# tanfolyamrobot.net
KiCad netlist of a schematic drawn in EAGLE
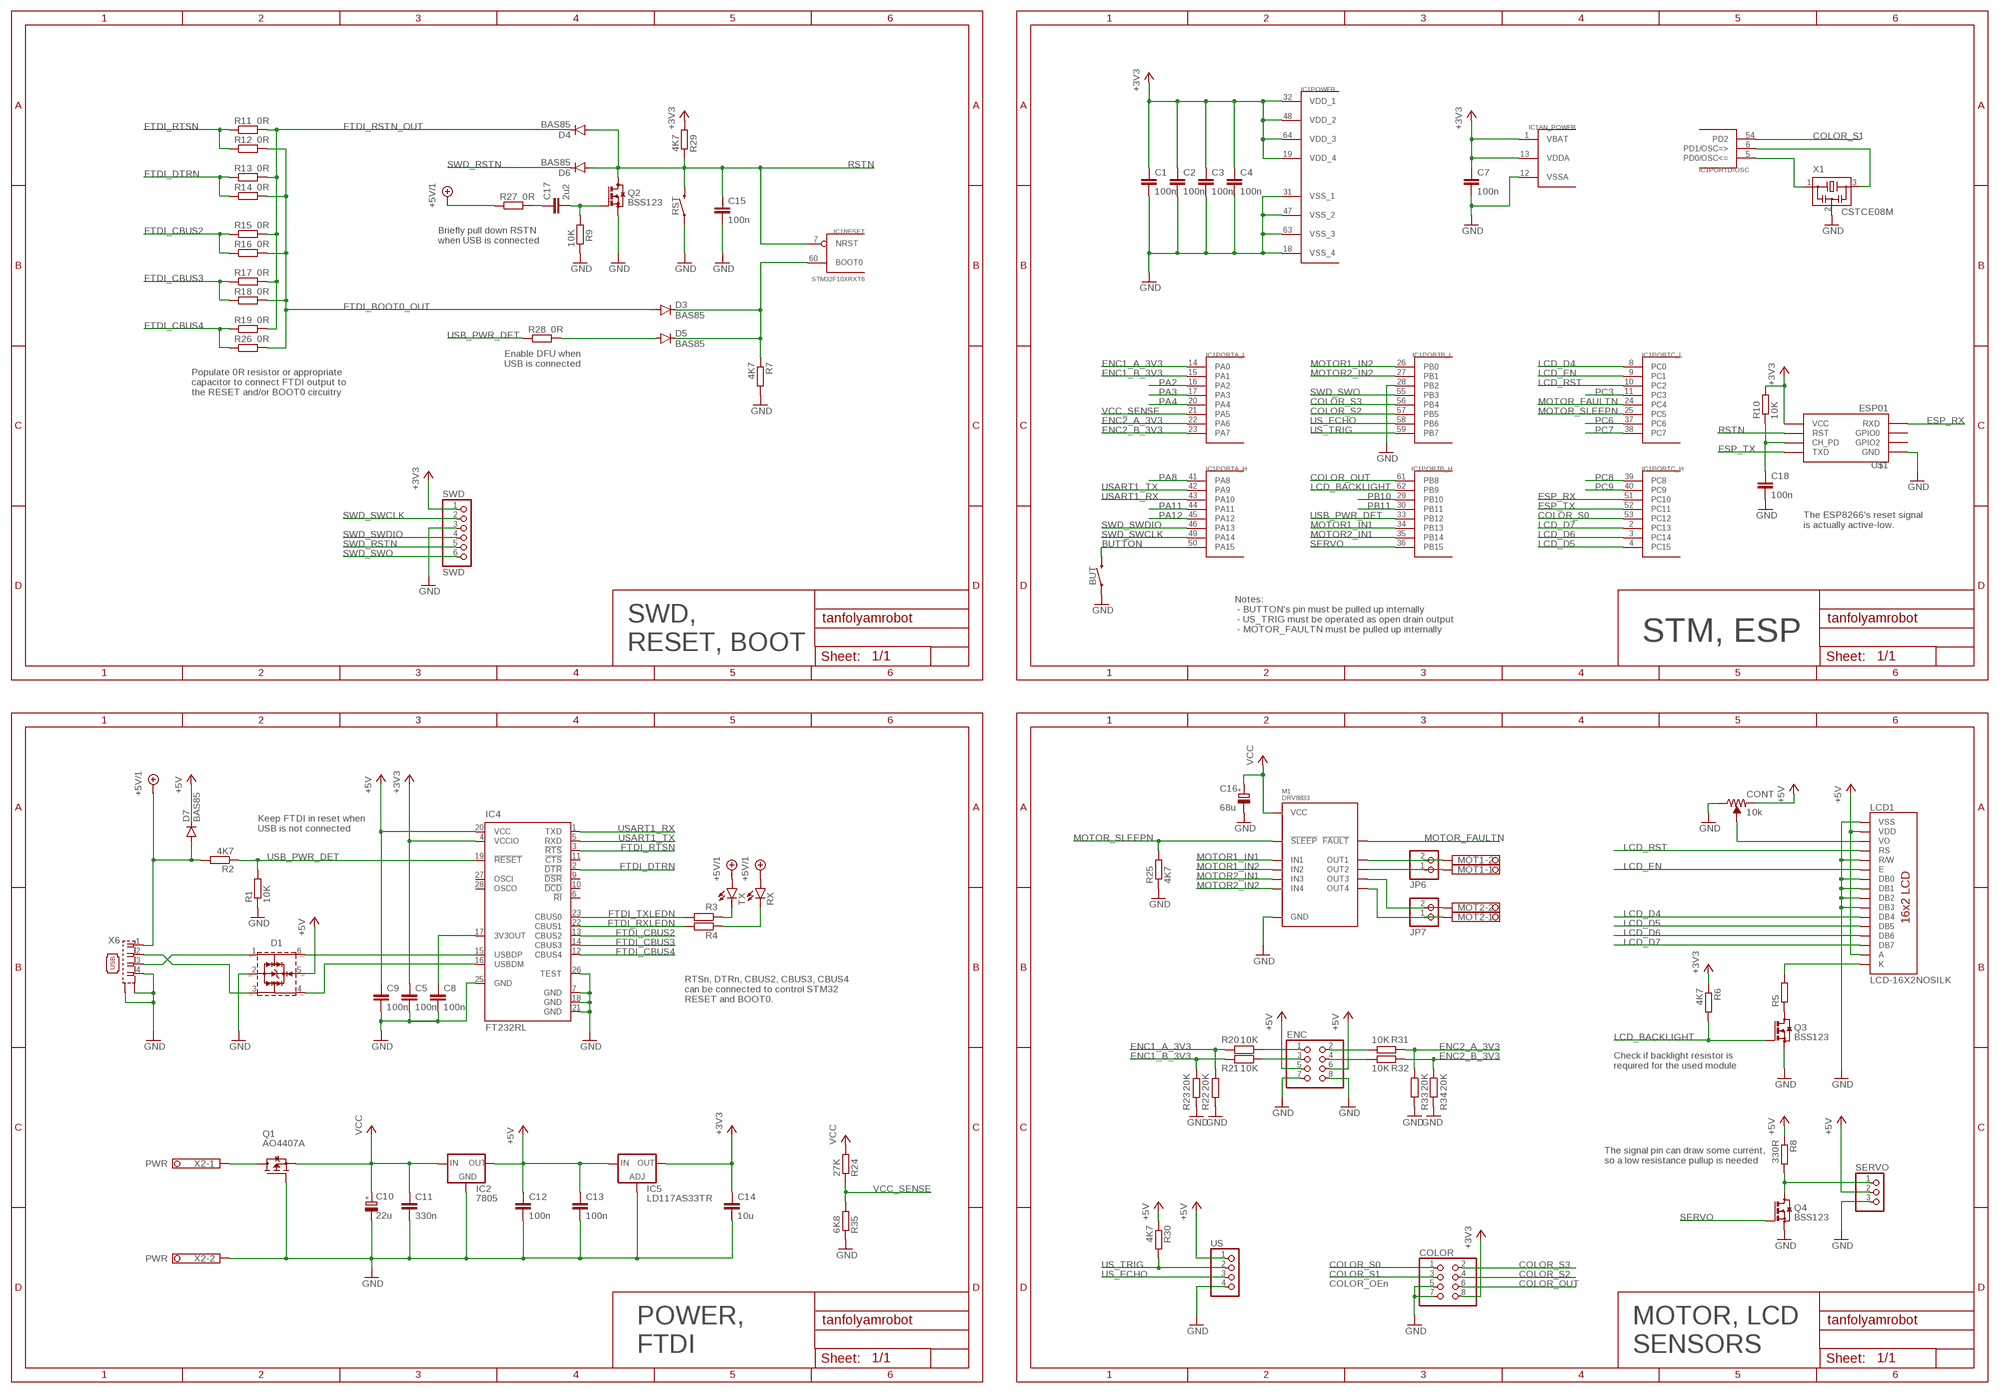
[diagram p0: schematic, sheet 1]

(export (version "E")
  (design (tool "Eeschema 10.0.6"))
  (components
    (comp (ref "BUT")
      (value "MOMENTARY-SWITCH-SPST-PTH-6.0MM")
      (footprint "eagle-import:TACTILE_SWITCH_PTH_6.0MM")
      (libsource (lib "eagle-import") (part "MOMENTARY-SWITCH-SPST-PTH-6.0MM"))
    )
    (comp (ref "C1")
      (value "100n")
      (footprint "eagle-import:C0603")
      (libsource (lib "eagle-import") (part "C-EUC0603"))
    )
    (comp (ref "C2")
      (value "100n")
      (footprint "eagle-import:C0603")
      (libsource (lib "eagle-import") (part "C-EUC0603"))
    )
    (comp (ref "C3")
      (value "100n")
      (footprint "eagle-import:C0603")
      (libsource (lib "eagle-import") (part "C-EUC0603"))
    )
    (comp (ref "C4")
      (value "100n")
      (footprint "eagle-import:C0603")
      (libsource (lib "eagle-import") (part "C-EUC0603"))
    )
    (comp (ref "C5")
      (value "100n")
      (footprint "eagle-import:C0603")
      (libsource (lib "eagle-import") (part "C-EUC0603"))
    )
    (comp (ref "C7")
      (value "100n")
      (footprint "eagle-import:C0603")
      (libsource (lib "eagle-import") (part "C-EUC0603"))
    )
    (comp (ref "C8")
      (value "100n")
      (footprint "eagle-import:C0603")
      (libsource (lib "eagle-import") (part "C-EUC0603"))
    )
    (comp (ref "C9")
      (value "100n")
      (footprint "eagle-import:C0603")
      (libsource (lib "eagle-import") (part "C-EUC0603"))
    )
    (comp (ref "C10")
      (value "22u")
      (footprint "eagle-import:B_3528-21R")
      (libsource (lib "eagle-import") (part "CPOL-EUB/3528-21R"))
    )
    (comp (ref "C11")
      (value "330n")
      (footprint "eagle-import:C0805K")
      (libsource (lib "eagle-import") (part "C-EUC0805K"))
    )
    (comp (ref "C12")
      (value "100n")
      (footprint "eagle-import:C0805K")
      (libsource (lib "eagle-import") (part "C-EUC0805K"))
    )
    (comp (ref "C13")
      (value "100n")
      (footprint "eagle-import:C0805K")
      (libsource (lib "eagle-import") (part "C-EUC0805K"))
    )
    (comp (ref "C14")
      (value "10u")
      (footprint "eagle-import:C0805K")
      (libsource (lib "eagle-import") (part "C-EUC0805K"))
    )
    (comp (ref "C15")
      (value "100n")
      (footprint "eagle-import:C0603")
      (libsource (lib "eagle-import") (part "C-EUC0603"))
    )
    (comp (ref "C16")
      (value "68u")
      (footprint "eagle-import:B_3528-21R")
      (libsource (lib "eagle-import") (part "CPOL-EUB/3528-21R"))
    )
    (comp (ref "C17")
      (value "2u2")
      (footprint "eagle-import:C0603")
      (libsource (lib "eagle-import") (part "C-EUC0603"))
    )
    (comp (ref "C18")
      (value "100n")
      (footprint "eagle-import:C0603")
      (libsource (lib "eagle-import") (part "C-EUC0603"))
    )
    (comp (ref "COLOR")
      (value "PINHD-2X4/90")
      (footprint "eagle-import:2X04_90")
      (libsource (lib "eagle-import") (part "PINHD-2X4/90"))
    )
    (comp (ref "CONT")
      (value "10k")
      (footprint "eagle-import:TRIMPOT-SMD-3MM-CLOSED")
      (libsource (lib "eagle-import") (part "TRIMPOT-SMD-3MM-CLOSED-1/8W-20%"))
    )
    (comp (ref "D1")
      (value "5Vdc")
      (footprint "eagle-import:WE-TVS_SOT23-6L")
      (libsource (lib "eagle-import") (part "WE-TVS-HS_SOT23-6L_82400102"))
    )
    (comp (ref "D3")
      (value "BAS85")
      (footprint "eagle-import:MICROMELF-W")
      (libsource (lib "eagle-import") (part "DIODE-MICROMELF-W"))
    )
    (comp (ref "D4")
      (value "BAS85")
      (footprint "eagle-import:MICROMELF-W")
      (libsource (lib "eagle-import") (part "DIODE-MICROMELF-W"))
    )
    (comp (ref "D5")
      (value "BAS85")
      (footprint "eagle-import:MICROMELF-W")
      (libsource (lib "eagle-import") (part "DIODE-MICROMELF-W"))
    )
    (comp (ref "D6")
      (value "BAS85")
      (footprint "eagle-import:MICROMELF-W")
      (libsource (lib "eagle-import") (part "DIODE-MICROMELF-W"))
    )
    (comp (ref "D7")
      (value "BAS85")
      (footprint "eagle-import:DO-214AC")
      (libsource (lib "eagle-import") (part "DIODE-DO-214AC"))
    )
    (comp (ref "ENC")
      (value "PINHD-2X4/90")
      (footprint "eagle-import:2X04_90")
      (libsource (lib "eagle-import") (part "PINHD-2X4/90"))
    )
    (comp (ref "IC1")
      (value "STM32F10XRXT6")
      (footprint "eagle-import:TQFP64")
      (libsource (lib "eagle-import") (part "STM32F10XRXT6"))
    )
    (comp (ref "IC2")
      (value "7805")
      (footprint "eagle-import:DPACK")
      (libsource (lib "eagle-import") (part "LP2950?CDT-3.0"))
    )
    (comp (ref "IC4")
      (value "FT232RL")
      (footprint "eagle-import:SSOP28")
      (libsource (lib "eagle-import") (part "FT232RL"))
    )
    (comp (ref "IC5")
      (value "LD117AS33TR")
      (footprint "eagle-import:SOT223")
      (libsource (lib "eagle-import") (part "LD117A?S33TR"))
    )
    (comp (ref "JP6")
      (value "PINHD-1X2")
      (footprint "eagle-import:1X02")
      (libsource (lib "eagle-import") (part "PINHD-1X2"))
    )
    (comp (ref "JP7")
      (value "PINHD-1X2")
      (footprint "eagle-import:1X02")
      (libsource (lib "eagle-import") (part "PINHD-1X2"))
    )
    (comp (ref "LCD1")
      (value "LCD-16X2NOSILK")
      (footprint "eagle-import:LCD-16X2_NOSILK")
      (libsource (lib "eagle-import") (part "LCD-16X2NOSILK"))
    )
    (comp (ref "M1")
      (value "DRV8833")
      (footprint "eagle-import:DRV8833_MODULE")
      (libsource (lib "eagle-import") (part "DRV8833"))
    )
    (comp (ref "MOT1")
      (value "PWR")
      (footprint "eagle-import:1751248")
      (libsource (lib "eagle-import") (part "1751248"))
    )
    (comp (ref "MOT2")
      (value "PWR")
      (footprint "eagle-import:1751248")
      (libsource (lib "eagle-import") (part "1751248"))
    )
    (comp (ref "Q1")
      (value "AO4407A")
      (footprint "eagle-import:SO-8")
      (libsource (lib "eagle-import") (part "BSO201SP"))
    )
    (comp (ref "Q2")
      (value "BSS123")
      (footprint "eagle-import:SOT23")
      (libsource (lib "eagle-import") (part "BSS123"))
    )
    (comp (ref "Q3")
      (value "BSS123")
      (footprint "eagle-import:SOT23")
      (libsource (lib "eagle-import") (part "BSS123"))
    )
    (comp (ref "Q4")
      (value "BSS123")
      (footprint "eagle-import:SOT23")
      (libsource (lib "eagle-import") (part "BSS123"))
    )
    (comp (ref "R1")
      (value "10K")
      (footprint "eagle-import:R0603")
      (libsource (lib "eagle-import") (part "R-EU_R0603"))
    )
    (comp (ref "R2")
      (value "4K7")
      (footprint "eagle-import:R0603")
      (libsource (lib "eagle-import") (part "R-EU_R0603"))
    )
    (comp (ref "R3")
      (value "R-EU_R0603")
      (footprint "eagle-import:R0603")
      (libsource (lib "eagle-import") (part "R-EU_R0603"))
    )
    (comp (ref "R4")
      (value "R-EU_R0603")
      (footprint "eagle-import:R0603")
      (libsource (lib "eagle-import") (part "R-EU_R0603"))
    )
    (comp (ref "R5")
      (value "R-EU_R0603")
      (footprint "eagle-import:R0603")
      (libsource (lib "eagle-import") (part "R-EU_R0603"))
    )
    (comp (ref "R6")
      (value "4K7")
      (footprint "eagle-import:R0603")
      (libsource (lib "eagle-import") (part "R-EU_R0603"))
    )
    (comp (ref "R7")
      (value "4K7")
      (footprint "eagle-import:R0603")
      (libsource (lib "eagle-import") (part "R-EU_R0603"))
    )
    (comp (ref "R8")
      (value "330R")
      (footprint "eagle-import:R0603")
      (libsource (lib "eagle-import") (part "R-EU_R0603"))
    )
    (comp (ref "R9")
      (value "10K")
      (footprint "eagle-import:R0603")
      (libsource (lib "eagle-import") (part "R-EU_R0603"))
    )
    (comp (ref "R10")
      (value "10K")
      (footprint "eagle-import:R0603")
      (libsource (lib "eagle-import") (part "R-EU_R0603"))
    )
    (comp (ref "R11")
      (value "0R")
      (footprint "eagle-import:R0603")
      (libsource (lib "eagle-import") (part "R-EU_R0603"))
    )
    (comp (ref "R12")
      (value "0R")
      (footprint "eagle-import:R0603")
      (libsource (lib "eagle-import") (part "R-EU_R0603"))
    )
    (comp (ref "R13")
      (value "0R")
      (footprint "eagle-import:R0603")
      (libsource (lib "eagle-import") (part "R-EU_R0603"))
    )
    (comp (ref "R14")
      (value "0R")
      (footprint "eagle-import:R0603")
      (libsource (lib "eagle-import") (part "R-EU_R0603"))
    )
    (comp (ref "R15")
      (value "0R")
      (footprint "eagle-import:R0603")
      (libsource (lib "eagle-import") (part "R-EU_R0603"))
    )
    (comp (ref "R16")
      (value "0R")
      (footprint "eagle-import:R0603")
      (libsource (lib "eagle-import") (part "R-EU_R0603"))
    )
    (comp (ref "R17")
      (value "0R")
      (footprint "eagle-import:R0603")
      (libsource (lib "eagle-import") (part "R-EU_R0603"))
    )
    (comp (ref "R18")
      (value "0R")
      (footprint "eagle-import:R0603")
      (libsource (lib "eagle-import") (part "R-EU_R0603"))
    )
    (comp (ref "R19")
      (value "0R")
      (footprint "eagle-import:R0603")
      (libsource (lib "eagle-import") (part "R-EU_R0603"))
    )
    (comp (ref "R20")
      (value "10K")
      (footprint "eagle-import:R0603")
      (libsource (lib "eagle-import") (part "R-EU_R0603"))
    )
    (comp (ref "R21")
      (value "10K")
      (footprint "eagle-import:R0603")
      (libsource (lib "eagle-import") (part "R-EU_R0603"))
    )
    (comp (ref "R22")
      (value "20K")
      (footprint "eagle-import:R0603")
      (libsource (lib "eagle-import") (part "R-EU_R0603"))
    )
    (comp (ref "R23")
      (value "20K")
      (footprint "eagle-import:R0603")
      (libsource (lib "eagle-import") (part "R-EU_R0603"))
    )
    (comp (ref "R24")
      (value "27K")
      (footprint "eagle-import:R0603")
      (libsource (lib "eagle-import") (part "R-EU_R0603"))
    )
    (comp (ref "R25")
      (value "4K7")
      (footprint "eagle-import:R0603")
      (libsource (lib "eagle-import") (part "R-EU_R0603"))
    )
    (comp (ref "R26")
      (value "0R")
      (footprint "eagle-import:R0603")
      (libsource (lib "eagle-import") (part "R-EU_R0603"))
    )
    (comp (ref "R27")
      (value "0R")
      (footprint "eagle-import:R0603")
      (libsource (lib "eagle-import") (part "R-EU_R0603"))
    )
    (comp (ref "R28")
      (value "0R")
      (footprint "eagle-import:R0603")
      (libsource (lib "eagle-import") (part "R-EU_R0603"))
    )
    (comp (ref "R29")
      (value "4K7")
      (footprint "eagle-import:R0603")
      (libsource (lib "eagle-import") (part "R-EU_R0603"))
    )
    (comp (ref "R30")
      (value "4K7")
      (footprint "eagle-import:R0603")
      (libsource (lib "eagle-import") (part "R-EU_R0603"))
    )
    (comp (ref "R31")
      (value "10K")
      (footprint "eagle-import:R0603")
      (libsource (lib "eagle-import") (part "R-EU_R0603"))
    )
    (comp (ref "R32")
      (value "10K")
      (footprint "eagle-import:R0603")
      (libsource (lib "eagle-import") (part "R-EU_R0603"))
    )
    (comp (ref "R33")
      (value "20K")
      (footprint "eagle-import:R0603")
      (libsource (lib "eagle-import") (part "R-EU_R0603"))
    )
    (comp (ref "R34")
      (value "20K")
      (footprint "eagle-import:R0603")
      (libsource (lib "eagle-import") (part "R-EU_R0603"))
    )
    (comp (ref "R35")
      (value "6K8")
      (footprint "eagle-import:R0603")
      (libsource (lib "eagle-import") (part "R-EU_R0603"))
    )
    (comp (ref "RST")
      (value "MOMENTARY-SWITCH-SPST-PTH-6.0MM")
      (footprint "eagle-import:TACTILE_SWITCH_PTH_6.0MM")
      (libsource (lib "eagle-import") (part "MOMENTARY-SWITCH-SPST-PTH-6.0MM"))
    )
    (comp (ref "RX")
      (value "LEDCHIP-LED0603")
      (footprint "eagle-import:CHIP-LED0603")
      (libsource (lib "eagle-import") (part "LEDCHIP-LED0603"))
    )
    (comp (ref "SERVO")
      (value "PINHD-1X3/90")
      (footprint "eagle-import:1X03_90")
      (libsource (lib "eagle-import") (part "PINHD-1X3/90"))
    )
    (comp (ref "SWD")
      (value "SWD")
      (footprint "eagle-import:1X06")
      (libsource (lib "eagle-import") (part "PINHD-1X6"))
    )
    (comp (ref "TX")
      (value "LEDCHIP-LED0603")
      (footprint "eagle-import:CHIP-LED0603")
      (libsource (lib "eagle-import") (part "LEDCHIP-LED0603"))
    )
    (comp (ref "U$1")
      (value "ESP01")
      (footprint "eagle-import:ESP01")
      (libsource (lib "eagle-import") (part "ESP01"))
    )
    (comp (ref "US")
      (value "PINHD-1X4/90")
      (footprint "eagle-import:1X04_90")
      (libsource (lib "eagle-import") (part "PINHD-1X4/90"))
    )
    (comp (ref "X1")
      (value "CSTCE08M")
      (footprint "eagle-import:CSTCE")
      (libsource (lib "eagle-import") (part "MURATA_CSTCE"))
    )
    (comp (ref "X2")
      (value "PWR")
      (footprint "eagle-import:1751248")
      (libsource (lib "eagle-import") (part "1751248"))
    )
    (comp (ref "X6")
      (value "KUSBVX-BS1N")
      (footprint "eagle-import:KUSBVX-BS1N")
      (libsource (lib "eagle-import") (part "KUSBVX-BS1N"))
    )
  )
  (nets
    (net (code "1") (name "+3V3") (class "Default")
      (node (ref "C1") (pin "1") (pinfunction "1_1") (pintype "passive"))
      (node (ref "C14") (pin "1") (pinfunction "1_1") (pintype "passive"))
      (node (ref "C2") (pin "1") (pinfunction "1_1") (pintype "passive"))
      (node (ref "C3") (pin "1") (pinfunction "1_1") (pintype "passive"))
      (node (ref "C4") (pin "1") (pinfunction "1_1") (pintype "passive"))
      (node (ref "C5") (pin "1") (pinfunction "1_1") (pintype "passive"))
      (node (ref "C7") (pin "1") (pinfunction "1_1") (pintype "passive"))
      (node (ref "COLOR") (pin "8") (pinfunction "8_8") (pintype "passive"))
      (node (ref "IC1") (pin "1") (pinfunction "VBAT_1") (pintype "power_in"))
      (node (ref "IC1") (pin "13") (pinfunction "VDDA_13") (pintype "power_in"))
      (node (ref "IC1") (pin "19") (pinfunction "VDD_4_19") (pintype "power_in"))
      (node (ref "IC1") (pin "32") (pinfunction "VDD_1_32") (pintype "power_in"))
      (node (ref "IC1") (pin "48") (pinfunction "VDD_2_48") (pintype "power_in"))
      (node (ref "IC1") (pin "64") (pinfunction "VDD_3_64") (pintype "power_in"))
      (node (ref "IC4") (pin "4") (pinfunction "VCCIO_4") (pintype "power_in"))
      (node (ref "IC5") (pin "4") (pinfunction "OUT_4") (pintype "passive"))
      (node (ref "R10") (pin "2") (pinfunction "2_2") (pintype "passive"))
      (node (ref "R29") (pin "1") (pinfunction "1_1") (pintype "passive"))
      (node (ref "R6") (pin "1") (pinfunction "1_1") (pintype "passive"))
      (node (ref "SWD") (pin "1") (pinfunction "1_1") (pintype "passive"))
      (node (ref "U$1") (pin "VCC") (pinfunction "VCC_VCC") (pintype "bidirectional"))
    )
    (net (code "2") (name "+5V") (class "Default")
      (node (ref "C12") (pin "1") (pinfunction "1_1") (pintype "passive"))
      (node (ref "C13") (pin "1") (pinfunction "1_1") (pintype "passive"))
      (node (ref "C9") (pin "1") (pinfunction "1_1") (pintype "passive"))
      (node (ref "CONT") (pin "1") (pinfunction "CCW_1") (pintype "passive"))
      (node (ref "D1") (pin "5") (pinfunction "VDD_5") (pintype "power_in"))
      (node (ref "D7") (pin "C") (pinfunction "C_C") (pintype "passive"))
      (node (ref "ENC") (pin "5") (pinfunction "5_5") (pintype "passive"))
      (node (ref "ENC") (pin "6") (pinfunction "6_6") (pintype "passive"))
      (node (ref "IC2") (pin "3") (pinfunction "OUT_3") (pintype "passive"))
      (node (ref "IC4") (pin "20") (pinfunction "VCC_20") (pintype "power_in"))
      (node (ref "IC5") (pin "3") (pinfunction "IN_3") (pintype "input"))
      (node (ref "LCD1") (pin "15") (pinfunction "A_15") (pintype "power_in"))
      (node (ref "LCD1") (pin "2") (pinfunction "VDD_2") (pintype "power_in"))
      (node (ref "R30") (pin "1") (pinfunction "1_1") (pintype "passive"))
      (node (ref "R8") (pin "1") (pinfunction "1_1") (pintype "passive"))
      (node (ref "SERVO") (pin "2") (pinfunction "2_2") (pintype "passive"))
      (node (ref "US") (pin "1") (pinfunction "1_1") (pintype "passive"))
    )
    (net (code "3") (name "+5V{slash}1") (class "Default")
      (node (ref "D7") (pin "A") (pinfunction "A_A") (pintype "passive"))
      (node (ref "R2") (pin "2") (pinfunction "2_2") (pintype "passive"))
      (node (ref "R27") (pin "1") (pinfunction "1_1") (pintype "passive"))
      (node (ref "RX") (pin "A") (pinfunction "A_A") (pintype "passive"))
      (node (ref "TX") (pin "A") (pinfunction "A_A") (pintype "passive"))
      (node (ref "X6") (pin "1") (pinfunction "1_1") (pintype "passive"))
    )
    (net (code "4") (name "/BUTTON") (class "Default")
      (node (ref "BUT") (pin "3") (pinfunction "2_3") (pintype "passive"))
      (node (ref "IC1") (pin "50") (pinfunction "PA15_50") (pintype "bidirectional"))
    )
    (net (code "5") (name "/COLOR_OUT") (class "Default")
      (node (ref "COLOR") (pin "6") (pinfunction "6_6") (pintype "passive"))
      (node (ref "IC1") (pin "61") (pinfunction "PB8_61") (pintype "bidirectional"))
    )
    (net (code "6") (name "/COLOR_S0") (class "Default")
      (node (ref "COLOR") (pin "1") (pinfunction "1_1") (pintype "passive"))
      (node (ref "IC1") (pin "53") (pinfunction "PC12_53") (pintype "bidirectional"))
    )
    (net (code "7") (name "/COLOR_S1") (class "Default")
      (node (ref "COLOR") (pin "3") (pinfunction "3_3") (pintype "passive"))
      (node (ref "IC1") (pin "54") (pinfunction "PD2_54") (pintype "bidirectional"))
    )
    (net (code "8") (name "/COLOR_S2") (class "Default")
      (node (ref "COLOR") (pin "4") (pinfunction "4_4") (pintype "passive"))
      (node (ref "IC1") (pin "57") (pinfunction "PB5_57") (pintype "bidirectional"))
    )
    (net (code "9") (name "/COLOR_S3") (class "Default")
      (node (ref "COLOR") (pin "2") (pinfunction "2_2") (pintype "passive"))
      (node (ref "IC1") (pin "56") (pinfunction "PB4_56") (pintype "bidirectional"))
    )
    (net (code "10") (name "/ENC1_A_3V3") (class "Default")
      (node (ref "IC1") (pin "14") (pinfunction "PA0_14") (pintype "bidirectional"))
      (node (ref "R20") (pin "2") (pinfunction "2_2") (pintype "passive"))
      (node (ref "R22") (pin "1") (pinfunction "1_1") (pintype "passive"))
    )
    (net (code "11") (name "/ENC1_B_3V3") (class "Default")
      (node (ref "IC1") (pin "15") (pinfunction "PA1_15") (pintype "bidirectional"))
      (node (ref "R21") (pin "2") (pinfunction "2_2") (pintype "passive"))
      (node (ref "R23") (pin "1") (pinfunction "1_1") (pintype "passive"))
    )
    (net (code "12") (name "/ENC2_A_3V3") (class "Default")
      (node (ref "IC1") (pin "22") (pinfunction "PA6_22") (pintype "bidirectional"))
      (node (ref "R31") (pin "2") (pinfunction "2_2") (pintype "passive"))
      (node (ref "R33") (pin "1") (pinfunction "1_1") (pintype "passive"))
    )
    (net (code "13") (name "/ENC2_B_3V3") (class "Default")
      (node (ref "IC1") (pin "23") (pinfunction "PA7_23") (pintype "bidirectional"))
      (node (ref "R32") (pin "2") (pinfunction "2_2") (pintype "passive"))
      (node (ref "R34") (pin "1") (pinfunction "1_1") (pintype "passive"))
    )
    (net (code "14") (name "/ESP_RX") (class "Default")
      (node (ref "IC1") (pin "51") (pinfunction "PC10_51") (pintype "bidirectional"))
      (node (ref "U$1") (pin "RX") (pinfunction "RXD_RX") (pintype "bidirectional"))
    )
    (net (code "15") (name "/ESP_TX") (class "Default")
      (node (ref "IC1") (pin "52") (pinfunction "PC11_52") (pintype "bidirectional"))
      (node (ref "U$1") (pin "TX") (pinfunction "TXD_TX") (pintype "bidirectional"))
    )
    (net (code "16") (name "/FTDI_BOOT0_OUT") (class "Default")
      (node (ref "D3") (pin "A") (pinfunction "A_A") (pintype "passive"))
      (node (ref "R12") (pin "2") (pinfunction "2_2") (pintype "passive"))
      (node (ref "R14") (pin "2") (pinfunction "2_2") (pintype "passive"))
      (node (ref "R16") (pin "2") (pinfunction "2_2") (pintype "passive"))
      (node (ref "R18") (pin "2") (pinfunction "2_2") (pintype "passive"))
      (node (ref "R26") (pin "2") (pinfunction "2_2") (pintype "passive"))
    )
    (net (code "17") (name "/FTDI_CBUS2") (class "Default")
      (node (ref "IC4") (pin "13") (pinfunction "CBUS2_13") (pintype "bidirectional"))
      (node (ref "R15") (pin "1") (pinfunction "1_1") (pintype "passive"))
      (node (ref "R16") (pin "1") (pinfunction "1_1") (pintype "passive"))
    )
    (net (code "18") (name "/FTDI_CBUS3") (class "Default")
      (node (ref "IC4") (pin "14") (pinfunction "CBUS3_14") (pintype "bidirectional"))
      (node (ref "R17") (pin "1") (pinfunction "1_1") (pintype "passive"))
      (node (ref "R18") (pin "1") (pinfunction "1_1") (pintype "passive"))
    )
    (net (code "19") (name "/FTDI_CBUS4") (class "Default")
      (node (ref "IC4") (pin "12") (pinfunction "CBUS4_12") (pintype "bidirectional"))
      (node (ref "R19") (pin "1") (pinfunction "1_1") (pintype "passive"))
      (node (ref "R26") (pin "1") (pinfunction "1_1") (pintype "passive"))
    )
    (net (code "20") (name "/FTDI_DTRN") (class "Default")
      (node (ref "IC4") (pin "2") (pinfunction "~{DTR}_2") (pintype "output"))
      (node (ref "R13") (pin "1") (pinfunction "1_1") (pintype "passive"))
      (node (ref "R14") (pin "1") (pinfunction "1_1") (pintype "passive"))
    )
    (net (code "21") (name "/FTDI_RSTN_OUT") (class "Default")
      (node (ref "D4") (pin "C") (pinfunction "C_C") (pintype "passive"))
      (node (ref "R11") (pin "2") (pinfunction "2_2") (pintype "passive"))
      (node (ref "R13") (pin "2") (pinfunction "2_2") (pintype "passive"))
      (node (ref "R15") (pin "2") (pinfunction "2_2") (pintype "passive"))
      (node (ref "R17") (pin "2") (pinfunction "2_2") (pintype "passive"))
      (node (ref "R19") (pin "2") (pinfunction "2_2") (pintype "passive"))
    )
    (net (code "22") (name "/FTDI_RTSN") (class "Default")
      (node (ref "IC4") (pin "3") (pinfunction "~{RTS}_3") (pintype "output"))
      (node (ref "R11") (pin "1") (pinfunction "1_1") (pintype "passive"))
      (node (ref "R12") (pin "1") (pinfunction "1_1") (pintype "passive"))
    )
    (net (code "23") (name "/FTDI_RXLEDN") (class "Default")
      (node (ref "IC4") (pin "22") (pinfunction "CBUS1_22") (pintype "bidirectional"))
      (node (ref "R4") (pin "2") (pinfunction "2_2") (pintype "passive"))
    )
    (net (code "24") (name "/FTDI_TXLEDN") (class "Default")
      (node (ref "IC4") (pin "23") (pinfunction "CBUS0_23") (pintype "bidirectional"))
      (node (ref "R3") (pin "2") (pinfunction "2_2") (pintype "passive"))
    )
    (net (code "25") (name "/LCD_BACKLIGHT") (class "Default")
      (node (ref "IC1") (pin "62") (pinfunction "PB9_62") (pintype "bidirectional"))
      (node (ref "Q3") (pin "1") (pinfunction "G_1") (pintype "passive"))
      (node (ref "R6") (pin "2") (pinfunction "2_2") (pintype "passive"))
    )
    (net (code "26") (name "/LCD_D4") (class "Default")
      (node (ref "IC1") (pin "8") (pinfunction "PC0_8") (pintype "bidirectional"))
      (node (ref "LCD1") (pin "11") (pinfunction "DB4_11") (pintype "bidirectional"))
    )
    (net (code "27") (name "/LCD_D5") (class "Default")
      (node (ref "IC1") (pin "4") (pinfunction "PC15_4") (pintype "bidirectional"))
      (node (ref "LCD1") (pin "12") (pinfunction "DB5_12") (pintype "bidirectional"))
    )
    (net (code "28") (name "/LCD_D6") (class "Default")
      (node (ref "IC1") (pin "3") (pinfunction "PC14_3") (pintype "bidirectional"))
      (node (ref "LCD1") (pin "13") (pinfunction "DB6_13") (pintype "bidirectional"))
    )
    (net (code "29") (name "/LCD_D7") (class "Default")
      (node (ref "IC1") (pin "2") (pinfunction "PC13_2") (pintype "bidirectional"))
      (node (ref "LCD1") (pin "14") (pinfunction "DB7_14") (pintype "bidirectional"))
    )
    (net (code "30") (name "/LCD_EN") (class "Default")
      (node (ref "IC1") (pin "9") (pinfunction "PC1_9") (pintype "bidirectional"))
      (node (ref "LCD1") (pin "6") (pinfunction "E_6") (pintype "input"))
    )
    (net (code "31") (name "/LCD_RST") (class "Default")
      (node (ref "IC1") (pin "10") (pinfunction "PC2_10") (pintype "bidirectional"))
      (node (ref "LCD1") (pin "4") (pinfunction "RS_4") (pintype "input"))
    )
    (net (code "32") (name "/MOTOR1_IN1") (class "Default")
      (node (ref "IC1") (pin "34") (pinfunction "PB13_34") (pintype "bidirectional"))
      (node (ref "M1") (pin "IN1") (pinfunction "IN1_IN1") (pintype "bidirectional"))
    )
    (net (code "33") (name "/MOTOR1_IN2") (class "Default")
      (node (ref "IC1") (pin "26") (pinfunction "PB0_26") (pintype "bidirectional"))
      (node (ref "M1") (pin "IN2") (pinfunction "IN2_IN2") (pintype "bidirectional"))
    )
    (net (code "34") (name "/MOTOR2_IN1") (class "Default")
      (node (ref "IC1") (pin "35") (pinfunction "PB14_35") (pintype "bidirectional"))
      (node (ref "M1") (pin "IN3") (pinfunction "IN3_IN3") (pintype "bidirectional"))
    )
    (net (code "35") (name "/MOTOR2_IN2") (class "Default")
      (node (ref "IC1") (pin "27") (pinfunction "PB1_27") (pintype "bidirectional"))
      (node (ref "M1") (pin "IN4") (pinfunction "IN4_IN4") (pintype "bidirectional"))
    )
    (net (code "36") (name "/MOTOR_FAULTN") (class "Default")
      (node (ref "IC1") (pin "24") (pinfunction "PC4_24") (pintype "bidirectional"))
      (node (ref "M1") (pin "!FAULT") (pinfunction "~{FAULT}_!FAULT") (pintype "bidirectional"))
    )
    (net (code "37") (name "/MOTOR_SLEEPN") (class "Default")
      (node (ref "IC1") (pin "25") (pinfunction "PC5_25") (pintype "bidirectional"))
      (node (ref "M1") (pin "!SLEEP") (pinfunction "~{SLEEP}_!SLEEP") (pintype "bidirectional"))
      (node (ref "R25") (pin "2") (pinfunction "2_2") (pintype "passive"))
    )
    (net (code "38") (name "/PA2") (class "Default")
      (node (ref "IC1") (pin "16") (pinfunction "PA2_16") (pintype "bidirectional"))
    )
    (net (code "39") (name "/PA3") (class "Default")
      (node (ref "IC1") (pin "17") (pinfunction "PA3_17") (pintype "bidirectional"))
    )
    (net (code "40") (name "/PA4") (class "Default")
      (node (ref "IC1") (pin "20") (pinfunction "PA4_20") (pintype "bidirectional"))
    )
    (net (code "41") (name "/PA8") (class "Default")
      (node (ref "IC1") (pin "41") (pinfunction "PA8_41") (pintype "bidirectional"))
    )
    (net (code "42") (name "/PA11") (class "Default")
      (node (ref "IC1") (pin "44") (pinfunction "PA11_44") (pintype "bidirectional"))
    )
    (net (code "43") (name "/PA12") (class "Default")
      (node (ref "IC1") (pin "45") (pinfunction "PA12_45") (pintype "bidirectional"))
    )
    (net (code "44") (name "/PB10") (class "Default")
      (node (ref "IC1") (pin "29") (pinfunction "PB10_29") (pintype "bidirectional"))
    )
    (net (code "45") (name "/PB11") (class "Default")
      (node (ref "IC1") (pin "30") (pinfunction "PB11_30") (pintype "bidirectional"))
    )
    (net (code "46") (name "/PC3") (class "Default")
      (node (ref "IC1") (pin "11") (pinfunction "PC3_11") (pintype "bidirectional"))
    )
    (net (code "47") (name "/PC6") (class "Default")
      (node (ref "IC1") (pin "37") (pinfunction "PC6_37") (pintype "bidirectional"))
    )
    (net (code "48") (name "/PC7") (class "Default")
      (node (ref "IC1") (pin "38") (pinfunction "PC7_38") (pintype "bidirectional"))
    )
    (net (code "49") (name "/PC8") (class "Default")
      (node (ref "IC1") (pin "39") (pinfunction "PC8_39") (pintype "bidirectional"))
    )
    (net (code "50") (name "/PC9") (class "Default")
      (node (ref "IC1") (pin "40") (pinfunction "PC9_40") (pintype "bidirectional"))
    )
    (net (code "51") (name "/RSTN") (class "Default")
      (node (ref "C15") (pin "1") (pinfunction "1_1") (pintype "passive"))
      (node (ref "D4") (pin "A") (pinfunction "A_A") (pintype "passive"))
      (node (ref "D6") (pin "A") (pinfunction "A_A") (pintype "passive"))
      (node (ref "IC1") (pin "7") (pinfunction "NRST_7") (pintype "input"))
      (node (ref "Q2") (pin "3") (pinfunction "D_3") (pintype "passive"))
      (node (ref "R29") (pin "2") (pinfunction "2_2") (pintype "passive"))
      (node (ref "RST") (pin "3") (pinfunction "2_3") (pintype "passive"))
      (node (ref "U$1") (pin "RST") (pinfunction "RST_RST") (pintype "bidirectional"))
    )
    (net (code "52") (name "/SERVO") (class "Default")
      (node (ref "IC1") (pin "36") (pinfunction "PB15_36") (pintype "bidirectional"))
      (node (ref "Q4") (pin "1") (pinfunction "G_1") (pintype "passive"))
    )
    (net (code "53") (name "/SWD_RSTN") (class "Default")
      (node (ref "D6") (pin "C") (pinfunction "C_C") (pintype "passive"))
      (node (ref "SWD") (pin "5") (pinfunction "5_5") (pintype "passive"))
    )
    (net (code "54") (name "/SWD_SWCLK") (class "Default")
      (node (ref "IC1") (pin "49") (pinfunction "PA14_49") (pintype "bidirectional"))
      (node (ref "SWD") (pin "2") (pinfunction "2_2") (pintype "passive"))
    )
    (net (code "55") (name "/SWD_SWDIO") (class "Default")
      (node (ref "IC1") (pin "46") (pinfunction "PA13_46") (pintype "bidirectional"))
      (node (ref "SWD") (pin "4") (pinfunction "4_4") (pintype "passive"))
    )
    (net (code "56") (name "/SWD_SWO") (class "Default")
      (node (ref "IC1") (pin "55") (pinfunction "PB3_55") (pintype "bidirectional"))
      (node (ref "SWD") (pin "6") (pinfunction "6_6") (pintype "passive"))
    )
    (net (code "57") (name "/USART1_RX") (class "Default")
      (node (ref "IC1") (pin "43") (pinfunction "PA10_43") (pintype "bidirectional"))
      (node (ref "IC4") (pin "1") (pinfunction "TXD_1") (pintype "output"))
    )
    (net (code "58") (name "/USART1_TX") (class "Default")
      (node (ref "IC1") (pin "42") (pinfunction "PA9_42") (pintype "bidirectional"))
      (node (ref "IC4") (pin "5") (pinfunction "RXD_5") (pintype "input"))
    )
    (net (code "59") (name "/USB_PWR_DET") (class "Default")
      (node (ref "IC1") (pin "33") (pinfunction "PB12_33") (pintype "bidirectional"))
      (node (ref "IC4") (pin "19") (pinfunction "~{RESET}_19") (pintype "input"))
      (node (ref "R1") (pin "2") (pinfunction "2_2") (pintype "passive"))
      (node (ref "R2") (pin "1") (pinfunction "1_1") (pintype "passive"))
      (node (ref "R28") (pin "1") (pinfunction "1_1") (pintype "passive"))
    )
    (net (code "60") (name "/US_ECHO") (class "Default")
      (node (ref "IC1") (pin "58") (pinfunction "PB6_58") (pintype "bidirectional"))
      (node (ref "US") (pin "3") (pinfunction "3_3") (pintype "passive"))
    )
    (net (code "61") (name "/US_TRIG") (class "Default")
      (node (ref "IC1") (pin "59") (pinfunction "PB7_59") (pintype "bidirectional"))
      (node (ref "R30") (pin "2") (pinfunction "2_2") (pintype "passive"))
      (node (ref "US") (pin "2") (pinfunction "2_2") (pintype "passive"))
    )
    (net (code "62") (name "/VCC_SENSE") (class "Default")
      (node (ref "IC1") (pin "21") (pinfunction "PA5_21") (pintype "bidirectional"))
      (node (ref "R24") (pin "2") (pinfunction "2_2") (pintype "passive"))
      (node (ref "R35") (pin "1") (pinfunction "1_1") (pintype "passive"))
    )
    (net (code "63") (name "GND") (class "Default")
      (node (ref "BUT") (pin "1") (pinfunction "1_1") (pintype "passive"))
      (node (ref "C1") (pin "2") (pinfunction "2_2") (pintype "passive"))
      (node (ref "C10") (pin "-") (pinfunction "-_-") (pintype "passive"))
      (node (ref "C11") (pin "2") (pinfunction "2_2") (pintype "passive"))
      (node (ref "C12") (pin "2") (pinfunction "2_2") (pintype "passive"))
      (node (ref "C13") (pin "2") (pinfunction "2_2") (pintype "passive"))
      (node (ref "C14") (pin "2") (pinfunction "2_2") (pintype "passive"))
      (node (ref "C15") (pin "2") (pinfunction "2_2") (pintype "passive"))
      (node (ref "C16") (pin "-") (pinfunction "-_-") (pintype "passive"))
      (node (ref "C18") (pin "2") (pinfunction "2_2") (pintype "passive"))
      (node (ref "C2") (pin "2") (pinfunction "2_2") (pintype "passive"))
      (node (ref "C3") (pin "2") (pinfunction "2_2") (pintype "passive"))
      (node (ref "C4") (pin "2") (pinfunction "2_2") (pintype "passive"))
      (node (ref "C5") (pin "2") (pinfunction "2_2") (pintype "passive"))
      (node (ref "C7") (pin "2") (pinfunction "2_2") (pintype "passive"))
      (node (ref "C8") (pin "2") (pinfunction "2_2") (pintype "passive"))
      (node (ref "C9") (pin "2") (pinfunction "2_2") (pintype "passive"))
      (node (ref "COLOR") (pin "5") (pinfunction "5_5") (pintype "passive"))
      (node (ref "COLOR") (pin "7") (pinfunction "7_7") (pintype "passive"))
      (node (ref "CONT") (pin "3") (pinfunction "CW_3") (pintype "passive"))
      (node (ref "D1") (pin "2") (pinfunction "GND_2") (pintype "power_in"))
      (node (ref "ENC") (pin "7") (pinfunction "7_7") (pintype "passive"))
      (node (ref "ENC") (pin "8") (pinfunction "8_8") (pintype "passive"))
      (node (ref "IC1") (pin "12") (pinfunction "VSSA_12") (pintype "power_in"))
      (node (ref "IC1") (pin "18") (pinfunction "VSS_4_18") (pintype "power_in"))
      (node (ref "IC1") (pin "28") (pinfunction "PB2_28") (pintype "bidirectional"))
      (node (ref "IC1") (pin "31") (pinfunction "VSS_1_31") (pintype "power_in"))
      (node (ref "IC1") (pin "47") (pinfunction "VSS_2_47") (pintype "power_in"))
      (node (ref "IC1") (pin "63") (pinfunction "VSS_3_63") (pintype "power_in"))
      (node (ref "IC2") (pin "4") (pinfunction "GND_4") (pintype "input"))
      (node (ref "IC4") (pin "18") (pinfunction "GND_18") (pintype "power_in"))
      (node (ref "IC4") (pin "21") (pinfunction "GND_21") (pintype "power_in"))
      (node (ref "IC4") (pin "25") (pinfunction "GND_25") (pintype "power_in"))
      (node (ref "IC4") (pin "26") (pinfunction "TEST_26") (pintype "input"))
      (node (ref "IC4") (pin "7") (pinfunction "GND_7") (pintype "power_in"))
      (node (ref "IC5") (pin "1") (pinfunction "ADJ_1") (pintype "input"))
      (node (ref "LCD1") (pin "1") (pinfunction "VSS_1") (pintype "power_in"))
      (node (ref "LCD1") (pin "10") (pinfunction "DB3_10") (pintype "bidirectional"))
      (node (ref "LCD1") (pin "5") (pinfunction "R/W_5") (pintype "input"))
      (node (ref "LCD1") (pin "7") (pinfunction "DB0_7") (pintype "bidirectional"))
      (node (ref "LCD1") (pin "8") (pinfunction "DB1_8") (pintype "bidirectional"))
      (node (ref "LCD1") (pin "9") (pinfunction "DB2_9") (pintype "bidirectional"))
      (node (ref "M1") (pin "GND") (pinfunction "GND_GND") (pintype "bidirectional"))
      (node (ref "Q1") (pin "4") (pinfunction "G_4") (pintype "passive"))
      (node (ref "Q2") (pin "2") (pinfunction "S_2") (pintype "passive"))
      (node (ref "Q3") (pin "2") (pinfunction "S_2") (pintype "passive"))
      (node (ref "Q4") (pin "2") (pinfunction "S_2") (pintype "passive"))
      (node (ref "R1") (pin "1") (pinfunction "1_1") (pintype "passive"))
      (node (ref "R22") (pin "2") (pinfunction "2_2") (pintype "passive"))
      (node (ref "R23") (pin "2") (pinfunction "2_2") (pintype "passive"))
      (node (ref "R25") (pin "1") (pinfunction "1_1") (pintype "passive"))
      (node (ref "R33") (pin "2") (pinfunction "2_2") (pintype "passive"))
      (node (ref "R34") (pin "2") (pinfunction "2_2") (pintype "passive"))
      (node (ref "R35") (pin "2") (pinfunction "2_2") (pintype "passive"))
      (node (ref "R7") (pin "2") (pinfunction "2_2") (pintype "passive"))
      (node (ref "R9") (pin "2") (pinfunction "2_2") (pintype "passive"))
      (node (ref "RST") (pin "1") (pinfunction "1_1") (pintype "passive"))
      (node (ref "SERVO") (pin "3") (pinfunction "3_3") (pintype "passive"))
      (node (ref "SWD") (pin "3") (pinfunction "3_3") (pintype "passive"))
      (node (ref "U$1") (pin "GND") (pinfunction "GND_GND") (pintype "bidirectional"))
      (node (ref "US") (pin "4") (pinfunction "4_4") (pintype "passive"))
      (node (ref "X1") (pin "2") (pinfunction "2_2") (pintype "passive"))
      (node (ref "X2") (pin "2") (pinfunction "K_2") (pintype "passive"))
      (node (ref "X6") (pin "4") (pinfunction "4_4") (pintype "passive"))
      (node (ref "X6") (pin "M1") (pinfunction "S1_M1") (pintype "passive"))
      (node (ref "X6") (pin "M2") (pinfunction "S2_M2") (pintype "passive"))
    )
    (net (code "64") (name "Net-(C17-Pad1)") (class "Default")
      (node (ref "C17") (pin "1") (pinfunction "1_1") (pintype "passive"))
      (node (ref "R27") (pin "2") (pinfunction "2_2") (pintype "passive"))
    )
    (net (code "65") (name "Net-(C18-Pad1)") (class "Default")
      (node (ref "C18") (pin "1") (pinfunction "1_1") (pintype "passive"))
      (node (ref "R10") (pin "1") (pinfunction "1_1") (pintype "passive"))
      (node (ref "U$1") (pin "CH_PD") (pinfunction "CH_PD_CH_PD") (pintype "bidirectional"))
    )
    (net (code "66") (name "Net-(CONT-WIPER)") (class "Default")
      (node (ref "CONT") (pin "2") (pinfunction "WIPER_2") (pintype "passive"))
      (node (ref "LCD1") (pin "3") (pinfunction "VO_3") (pintype "bidirectional"))
    )
    (net (code "67") (name "Net-(D1-I{slash}O1)") (class "Default")
      (node (ref "D1") (pin "1") (pinfunction "I/O1_1") (pintype "bidirectional"))
      (node (ref "X6") (pin "3") (pinfunction "3_3") (pintype "passive"))
    )
    (net (code "68") (name "Net-(D1-I{slash}O2)") (class "Default")
      (node (ref "D1") (pin "3") (pinfunction "I/O2_3") (pintype "bidirectional"))
      (node (ref "X6") (pin "2") (pinfunction "2_2") (pintype "passive"))
    )
    (net (code "69") (name "Net-(D1-I{slash}O3)") (class "Default")
      (node (ref "D1") (pin "6") (pinfunction "I/O3_6") (pintype "bidirectional"))
      (node (ref "IC4") (pin "15") (pinfunction "USBDP_15") (pintype "bidirectional"))
    )
    (net (code "70") (name "Net-(D1-I{slash}O4)") (class "Default")
      (node (ref "D1") (pin "4") (pinfunction "I/O4_4") (pintype "bidirectional"))
      (node (ref "IC4") (pin "16") (pinfunction "USBDM_16") (pintype "bidirectional"))
    )
    (net (code "71") (name "Net-(D5-PadA)") (class "Default")
      (node (ref "D5") (pin "A") (pinfunction "A_A") (pintype "passive"))
      (node (ref "R28") (pin "2") (pinfunction "2_2") (pintype "passive"))
    )
    (net (code "72") (name "Net-(ENC-Pad1)") (class "Default")
      (node (ref "ENC") (pin "1") (pinfunction "1_1") (pintype "passive"))
      (node (ref "R20") (pin "1") (pinfunction "1_1") (pintype "passive"))
    )
    (net (code "73") (name "Net-(ENC-Pad2)") (class "Default")
      (node (ref "ENC") (pin "2") (pinfunction "2_2") (pintype "passive"))
      (node (ref "R31") (pin "1") (pinfunction "1_1") (pintype "passive"))
    )
    (net (code "74") (name "Net-(ENC-Pad3)") (class "Default")
      (node (ref "ENC") (pin "3") (pinfunction "3_3") (pintype "passive"))
      (node (ref "R21") (pin "1") (pinfunction "1_1") (pintype "passive"))
    )
    (net (code "75") (name "Net-(ENC-Pad4)") (class "Default")
      (node (ref "ENC") (pin "4") (pinfunction "4_4") (pintype "passive"))
      (node (ref "R32") (pin "1") (pinfunction "1_1") (pintype "passive"))
    )
    (net (code "76") (name "Net-(IC1H-PD0{slash}OSC<=)") (class "Default")
      (node (ref "IC1") (pin "5") (pinfunction "PD0/OSC<=_5") (pintype "bidirectional"))
      (node (ref "X1") (pin "1") (pinfunction "1_1") (pintype "passive"))
    )
    (net (code "77") (name "Net-(IC1H-PD1{slash}OSC=>)") (class "Default")
      (node (ref "IC1") (pin "6") (pinfunction "PD1/OSC=>_6") (pintype "bidirectional"))
      (node (ref "X1") (pin "3") (pinfunction "3_3") (pintype "passive"))
    )
    (net (code "78") (name "Net-(IC1J-BOOT0)") (class "Default")
      (node (ref "D3") (pin "C") (pinfunction "C_C") (pintype "passive"))
      (node (ref "D5") (pin "C") (pinfunction "C_C") (pintype "passive"))
      (node (ref "IC1") (pin "60") (pinfunction "BOOT0_60") (pintype "input"))
      (node (ref "R7") (pin "1") (pinfunction "1_1") (pintype "passive"))
    )
    (net (code "79") (name "Net-(IC4-3V3OUT)") (class "Default")
      (node (ref "C8") (pin "1") (pinfunction "1_1") (pintype "passive"))
      (node (ref "IC4") (pin "17") (pinfunction "3V3OUT_17") (pintype "output"))
    )
    (net (code "80") (name "Net-(LCD1-K)") (class "Default")
      (node (ref "LCD1") (pin "16") (pinfunction "K_16") (pintype "power_in"))
      (node (ref "R5") (pin "2") (pinfunction "2_2") (pintype "passive"))
    )
    (net (code "81") (name "Net-(MOT1A-K)") (class "Default")
      (node (ref "JP6") (pin "1") (pinfunction "1_1") (pintype "passive"))
      (node (ref "M1") (pin "OUT2") (pinfunction "OUT2_OUT2") (pintype "bidirectional"))
      (node (ref "MOT1") (pin "1") (pinfunction "K_1") (pintype "passive"))
    )
    (net (code "82") (name "Net-(MOT1B-K)") (class "Default")
      (node (ref "JP6") (pin "2") (pinfunction "2_2") (pintype "passive"))
      (node (ref "M1") (pin "OUT1") (pinfunction "OUT1_OUT1") (pintype "bidirectional"))
      (node (ref "MOT1") (pin "2") (pinfunction "K_2") (pintype "passive"))
    )
    (net (code "83") (name "Net-(MOT2A-K)") (class "Default")
      (node (ref "JP7") (pin "1") (pinfunction "1_1") (pintype "passive"))
      (node (ref "M1") (pin "OUT4") (pinfunction "OUT4_OUT4") (pintype "bidirectional"))
      (node (ref "MOT2") (pin "1") (pinfunction "K_1") (pintype "passive"))
    )
    (net (code "84") (name "Net-(MOT2B-K)") (class "Default")
      (node (ref "JP7") (pin "2") (pinfunction "2_2") (pintype "passive"))
      (node (ref "M1") (pin "OUT3") (pinfunction "OUT3_OUT3") (pintype "bidirectional"))
      (node (ref "MOT2") (pin "2") (pinfunction "K_2") (pintype "passive"))
    )
    (net (code "85") (name "Net-(Q2-G)") (class "Default")
      (node (ref "C17") (pin "2") (pinfunction "2_2") (pintype "passive"))
      (node (ref "Q2") (pin "1") (pinfunction "G_1") (pintype "passive"))
      (node (ref "R9") (pin "1") (pinfunction "1_1") (pintype "passive"))
    )
    (net (code "86") (name "Net-(Q3-D)") (class "Default")
      (node (ref "Q3") (pin "3") (pinfunction "D_3") (pintype "passive"))
      (node (ref "R5") (pin "1") (pinfunction "1_1") (pintype "passive"))
    )
    (net (code "87") (name "Net-(Q4-D)") (class "Default")
      (node (ref "Q4") (pin "3") (pinfunction "D_3") (pintype "passive"))
      (node (ref "R8") (pin "2") (pinfunction "2_2") (pintype "passive"))
      (node (ref "SERVO") (pin "1") (pinfunction "1_1") (pintype "passive"))
    )
    (net (code "88") (name "Net-(R3-Pad1)") (class "Default")
      (node (ref "R3") (pin "1") (pinfunction "1_1") (pintype "passive"))
      (node (ref "TX") (pin "C") (pinfunction "C_C") (pintype "passive"))
    )
    (net (code "89") (name "Net-(R4-Pad1)") (class "Default")
      (node (ref "R4") (pin "1") (pinfunction "1_1") (pintype "passive"))
      (node (ref "RX") (pin "C") (pinfunction "C_C") (pintype "passive"))
    )
    (net (code "90") (name "Net-(X2A-K)") (class "Default")
      (node (ref "Q1") (pin "5") (pinfunction "D_5") (pintype "passive"))
      (node (ref "Q1") (pin "6") (pinfunction "D_6") (pintype "passive"))
      (node (ref "Q1") (pin "7") (pinfunction "D_7") (pintype "passive"))
      (node (ref "Q1") (pin "8") (pinfunction "D_8") (pintype "passive"))
      (node (ref "X2") (pin "1") (pinfunction "K_1") (pintype "passive"))
    )
    (net (code "91") (name "VCC") (class "Default")
      (node (ref "C10") (pin "+") (pinfunction "+_+") (pintype "passive"))
      (node (ref "C11") (pin "1") (pinfunction "1_1") (pintype "passive"))
      (node (ref "C16") (pin "+") (pinfunction "+_+") (pintype "passive"))
      (node (ref "IC2") (pin "1") (pinfunction "IN_1") (pintype "input"))
      (node (ref "M1") (pin "VCC") (pinfunction "VCC_VCC") (pintype "bidirectional"))
      (node (ref "Q1") (pin "1") (pinfunction "S_1") (pintype "passive"))
      (node (ref "Q1") (pin "2") (pinfunction "S_2") (pintype "passive"))
      (node (ref "Q1") (pin "3") (pinfunction "S_3") (pintype "passive"))
      (node (ref "R24") (pin "1") (pinfunction "1_1") (pintype "passive"))
    )
    (net (code "92") (name "unconnected-(IC4-OSCI-Pad27)") (class "Default")
      (node (ref "IC4") (pin "27") (pinfunction "OSCI_27") (pintype "input"))
    )
    (net (code "93") (name "unconnected-(IC4-OSCO-Pad28)") (class "Default")
      (node (ref "IC4") (pin "28") (pinfunction "OSCO_28") (pintype "output"))
    )
    (net (code "94") (name "unconnected-(IC4-~{CTS}-Pad11)") (class "Default")
      (node (ref "IC4") (pin "11") (pinfunction "~{CTS}_11") (pintype "input"))
    )
    (net (code "95") (name "unconnected-(IC4-~{DCD}-Pad10)") (class "Default")
      (node (ref "IC4") (pin "10") (pinfunction "~{DCD}_10") (pintype "input"))
    )
    (net (code "96") (name "unconnected-(IC4-~{DSR}-Pad9)") (class "Default")
      (node (ref "IC4") (pin "9") (pinfunction "~{DSR}_9") (pintype "input"))
    )
    (net (code "97") (name "unconnected-(IC4-~{RI}-Pad6)") (class "Default")
      (node (ref "IC4") (pin "6") (pinfunction "~{RI}_6") (pintype "input"))
    )
    (net (code "98") (name "unconnected-(U$1-PadGPIO0)") (class "Default")
      (node (ref "U$1") (pin "GPIO0") (pinfunction "GPIO0_GPIO0") (pintype "bidirectional"))
    )
    (net (code "99") (name "unconnected-(U$1-PadGPIO2)") (class "Default")
      (node (ref "U$1") (pin "GPIO2") (pinfunction "GPIO2_GPIO2") (pintype "bidirectional"))
    )
  )
)
